# Sensors.net
KiCad netlist of a schematic drawn in Altium Designer
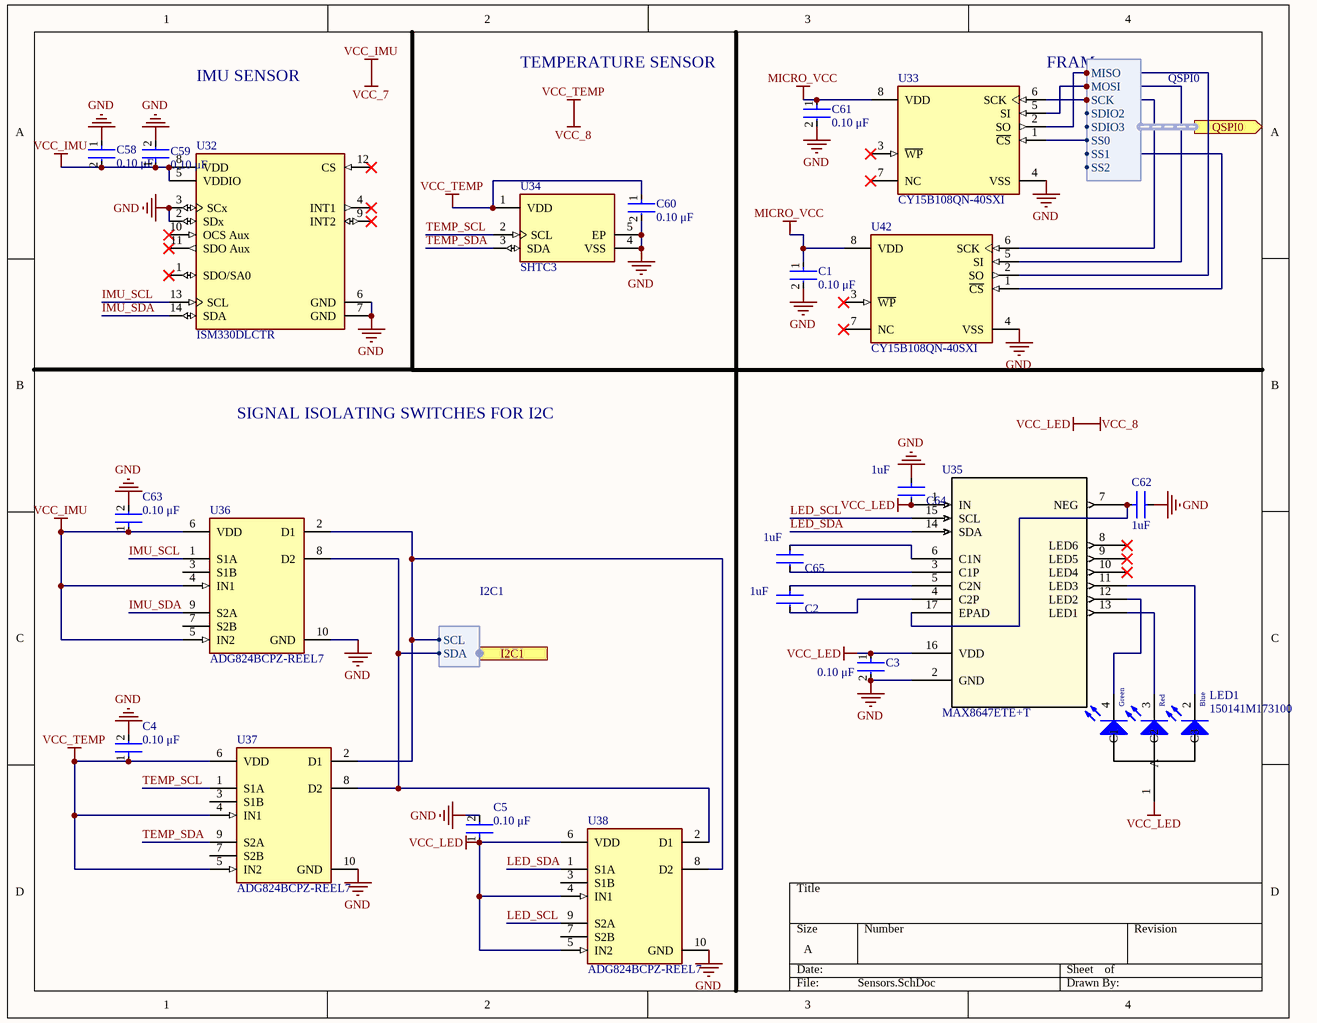
[diagram p0: Sensors.SchDoc]

(export (version "E")
  (design (tool "Eeschema 10.0.6"))
  (components
    (comp (ref "C1")
      (value "C0402C104K8PACTU")
      (footprint "FP-C0402-BB-MFG")
      (description "CAP CER 0.1UF 10V X5R 0402")
      (fields
        (field (name "CAPACITANCE") "0.10 μF")
        (field (name "MANUFACTURER") "Kemet")
        (field (name "TOLERANCE") "0.1")
      )
      (libsource (lib "Altium Content Vault") (part "b4654b650e69147ec39a6b967a45e02"))
    )
    (comp (ref "C2")
      (value "GRT155R61C105KE01J")
      (footprint "FP-GRM15-0_1-MFG")
      (description "CAP CER 1UF 10V X5R 0402")
      (fields
        (field (name "OCTOPART") "https://octopart.com/grm155r61a105ke15d-murata-197442")
        (field (name "MANUFACTURER PART NUMBER") "GRM155R61A105KE15D")
        (field (name "CAPACITANCE") "1uF")
      )
      (libsource (lib "Altium Content Vault") (part "02cd4be3c70576c341d710602a673aa"))
    )
    (comp (ref "C3")
      (value "C0402C104K8PACTU")
      (footprint "FP-C0402-BB-MFG")
      (description "CAP CER 0.1UF 10V X5R 0402")
      (fields
        (field (name "CAPACITANCE") "0.10 μF")
        (field (name "MANUFACTURER") "Kemet")
        (field (name "TOLERANCE") "0.1")
      )
      (libsource (lib "Altium Content Vault") (part "b4654b650e69147ec39a6b967a45e02"))
    )
    (comp (ref "C4")
      (value "C0402C104K8PACTU")
      (footprint "FP-C0402-BB-MFG")
      (description "CAP CER 0.1UF 10V X5R 0402")
      (fields
        (field (name "CAPACITANCE") "0.10 μF")
        (field (name "MANUFACTURER") "Kemet")
        (field (name "TOLERANCE") "0.1")
      )
      (libsource (lib "Altium Content Vault") (part "b4654b650e69147ec39a6b967a45e02"))
    )
    (comp (ref "C5")
      (value "C0402C104K8PACTU")
      (footprint "FP-C0402-BB-MFG")
      (description "CAP CER 0.1UF 10V X5R 0402")
      (fields
        (field (name "CAPACITANCE") "0.10 μF")
        (field (name "MANUFACTURER") "Kemet")
        (field (name "TOLERANCE") "0.1")
      )
      (libsource (lib "Altium Content Vault") (part "b4654b650e69147ec39a6b967a45e02"))
    )
    (comp (ref "C58")
      (value "C0402C104K8PACTU")
      (footprint "FP-C0402-BB-MFG")
      (description "CAP CER 0.1UF 10V X5R 0402")
      (fields
        (field (name "CAPACITANCE") "0.10 μF")
        (field (name "MANUFACTURER") "Kemet")
        (field (name "TOLERANCE") "0.1")
      )
      (libsource (lib "Altium Content Vault") (part "b4654b650e69147ec39a6b967a45e02"))
    )
    (comp (ref "C59")
      (value "C0402C104K8PACTU")
      (footprint "FP-C0402-BB-MFG")
      (description "CAP CER 0.1UF 10V X5R 0402")
      (fields
        (field (name "CAPACITANCE") "0.10 μF")
        (field (name "MANUFACTURER") "Kemet")
        (field (name "TOLERANCE") "0.1")
      )
      (libsource (lib "Altium Content Vault") (part "b4654b650e69147ec39a6b967a45e02"))
    )
    (comp (ref "C60")
      (value "C0402C104K8PACTU")
      (footprint "FP-C0402-BB-MFG")
      (description "CAP CER 0.1UF 10V X5R 0402")
      (fields
        (field (name "CAPACITANCE") "0.10 μF")
        (field (name "MANUFACTURER") "Kemet")
        (field (name "TOLERANCE") "0.1")
      )
      (libsource (lib "Altium Content Vault") (part "b4654b650e69147ec39a6b967a45e02"))
    )
    (comp (ref "C61")
      (value "C0402C104K8PACTU")
      (footprint "FP-C0402-BB-MFG")
      (description "CAP CER 0.1UF 10V X5R 0402")
      (fields
        (field (name "CAPACITANCE") "0.10 μF")
        (field (name "MANUFACTURER") "Kemet")
        (field (name "TOLERANCE") "0.1")
      )
      (libsource (lib "Altium Content Vault") (part "b4654b650e69147ec39a6b967a45e02"))
    )
    (comp (ref "C62")
      (value "GRT155R61C105KE01J")
      (footprint "FP-GRM15-0_1-MFG")
      (description "CAP CER 1UF 10V X5R 0402")
      (fields
        (field (name "OCTOPART") "https://octopart.com/grm155r61a105ke15d-murata-197442")
        (field (name "MANUFACTURER PART NUMBER") "GRM155R61A105KE15D")
        (field (name "CAPACITANCE") "1uF")
      )
      (libsource (lib "Altium Content Vault") (part "02cd4be3c70576c341d710602a673aa"))
    )
    (comp (ref "C63")
      (value "C0402C104K8PACTU")
      (footprint "FP-C0402-BB-MFG")
      (description "CAP CER 0.1UF 10V X5R 0402")
      (fields
        (field (name "CAPACITANCE") "0.10 μF")
        (field (name "MANUFACTURER") "Kemet")
        (field (name "TOLERANCE") "0.1")
      )
      (libsource (lib "Altium Content Vault") (part "b4654b650e69147ec39a6b967a45e02"))
    )
    (comp (ref "C64")
      (value "GRT155R61C105KE01J")
      (footprint "FP-GRM15-0_1-MFG")
      (description "CAP CER 1UF 10V X5R 0402")
      (fields
        (field (name "OCTOPART") "https://octopart.com/grm155r61a105ke15d-murata-197442")
        (field (name "MANUFACTURER PART NUMBER") "GRM155R61A105KE15D")
        (field (name "CAPACITANCE") "1uF")
      )
      (libsource (lib "Altium Content Vault") (part "02cd4be3c70576c341d710602a673aa"))
    )
    (comp (ref "C65")
      (value "GRT155R61C105KE01J")
      (footprint "FP-GRM15-0_1-MFG")
      (description "CAP CER 1UF 10V X5R 0402")
      (fields
        (field (name "OCTOPART") "https://octopart.com/grm155r61a105ke15d-murata-197442")
        (field (name "MANUFACTURER PART NUMBER") "GRM155R61A105KE15D")
        (field (name "CAPACITANCE") "1uF")
      )
      (libsource (lib "Altium Content Vault") (part "02cd4be3c70576c341d710602a673aa"))
    )
    (comp (ref "LED1")
      (value "150141M173100")
      (footprint "3528_A")
      (description "SMD Full-Color Top LED, WL-SFTW, Red & Green & Blue")
      (fields (field (name "MANUFACTURER") "Wuerth Elektronik"))
      (libsource (lib "Altium Content Vault") (part "WE-LED_RGB_A1B2R3G4-4"))
    )
    (comp (ref "U32")
      (value "ISM330DLCTR")
      (footprint "FP-LGA-14L-DM00249496-MFG")
      (description "INEMO INERTIAL MODULE")
      (fields
        (field (name "MANUFACTURER") "STMicroelectronics")
        (field (name "OCTOPART") "https://octopart.com/ism330dlctr-stmicroelectronics-85149243")
      )
      (libsource (lib "Altium Content Vault") (part "7cb83b91da826bd22f6a735c633f5ac"))
    )
    (comp (ref "U33")
      (value "CY15B108QN-40SXI")
      (footprint "FP-001-85261-IPC_C")
      (description "IC FRAM 8MBIT 40MHZ 8EIAJ")
      (libsource (lib "Altium Content Vault") (part "94cc5f17500dd1907c0ebdcd3efa3d4"))
    )
    (comp (ref "U34")
      (value "SHTC3")
      (footprint "FP-SHTC3-MFG")
      (description "SENSOR HUMI/TEMP I2C 2% SMD")
      (fields
        (field (name "MANUFACTURER") "Sensirion")
        (field (name "OCTOPART") "https://octopart.com/shtc3-sensirion-91912225")
      )
      (libsource (lib "Altium Content Vault") (part "92e21da4ceb1e434b50171ab113565b"))
    )
    (comp (ref "U35")
      (value "MAX8647ETE+T")
      (footprint "21-0136_T1633+5_MXM-L")
      (description "No Description Available")
      (fields (field (name "COPYRIGHT") "Copyright (C) 2021 Accelerated Designs. All rights reserved"))
      (libsource (lib "2021-07-18_11-49-46") (part "MAX8647ETE+T"))
    )
    (comp (ref "U36")
      (value "ADG824BCPZ-REEL7")
      (footprint "FP-CP-10-10-MFG")
      (description "IC SWITCH DUAL SPDT 10LFCSP")
      (fields
        (field (name "OCTOPART") "https://octopart.com/adg824bcpz-reel7-analog+devices-12410880")
        (field (name "MANUFACTURER") "Analog Devices")
      )
      (libsource (lib "Altium Content Vault") (part "750f7653eda72c1ba3820f182f788e1"))
    )
    (comp (ref "U37")
      (value "ADG824BCPZ-REEL7")
      (footprint "FP-CP-10-10-MFG")
      (description "IC SWITCH DUAL SPDT 10LFCSP")
      (fields
        (field (name "OCTOPART") "https://octopart.com/adg824bcpz-reel7-analog+devices-12410880")
        (field (name "MANUFACTURER") "Analog Devices")
      )
      (libsource (lib "Altium Content Vault") (part "750f7653eda72c1ba3820f182f788e1"))
    )
    (comp (ref "U38")
      (value "ADG824BCPZ-REEL7")
      (footprint "FP-CP-10-10-MFG")
      (description "IC SWITCH DUAL SPDT 10LFCSP")
      (fields
        (field (name "OCTOPART") "https://octopart.com/adg824bcpz-reel7-analog+devices-12410880")
        (field (name "MANUFACTURER") "Analog Devices")
      )
      (libsource (lib "Altium Content Vault") (part "750f7653eda72c1ba3820f182f788e1"))
    )
    (comp (ref "U42")
      (value "CY15B108QN-40SXI")
      (footprint "FP-001-85261-IPC_C")
      (description "IC FRAM 8MBIT 40MHZ 8EIAJ")
      (libsource (lib "Altium Content Vault") (part "94cc5f17500dd1907c0ebdcd3efa3d4"))
    )
  )
  (nets
    (net (code "3") (name "/IMU_SCL") (class "Default")
      (node (ref "U32") (pin "13") (pinfunction "SCL_13") (pintype "input"))
      (node (ref "U36") (pin "1") (pinfunction "S1A_1") (pintype "passive"))
    )
    (net (code "4") (name "/IMU_SDA") (class "Default")
      (node (ref "U32") (pin "14") (pinfunction "SDA_14") (pintype "bidirectional"))
      (node (ref "U36") (pin "9") (pinfunction "S2A_9") (pintype "passive"))
    )
    (net (code "5") (name "/LED_SCL") (class "Default")
      (node (ref "U35") (pin "15") (pinfunction "SCL_15") (pintype "input"))
      (node (ref "U38") (pin "9") (pinfunction "S2A_9") (pintype "passive"))
    )
    (net (code "6") (name "/LED_SDA") (class "Default")
      (node (ref "U35") (pin "14") (pinfunction "SDA_14") (pintype "input"))
      (node (ref "U38") (pin "1") (pinfunction "S1A_1") (pintype "passive"))
    )
    (net (code "7") (name "/MISO") (class "Default")
      (node (ref "U33") (pin "2") (pinfunction "SO_2") (pintype "output"))
      (node (ref "U42") (pin "2") (pinfunction "SO_2") (pintype "output"))
    )
    (net (code "8") (name "/MOSI") (class "Default")
      (node (ref "U33") (pin "5") (pinfunction "SI_5") (pintype "input"))
      (node (ref "U42") (pin "5") (pinfunction "SI_5") (pintype "input"))
    )
    (net (code "9") (name "/SCK") (class "Default")
      (node (ref "U33") (pin "6") (pinfunction "SCK_6") (pintype "input"))
      (node (ref "U42") (pin "6") (pinfunction "SCK_6") (pintype "input"))
    )
    (net (code "10") (name "/SCL") (class "Default")
      (node (ref "U36") (pin "2") (pinfunction "D1_2") (pintype "passive"))
      (node (ref "U37") (pin "2") (pinfunction "D1_2") (pintype "passive"))
      (node (ref "U38") (pin "8") (pinfunction "D2_8") (pintype "passive"))
    )
    (net (code "11") (name "/SDA") (class "Default")
      (node (ref "U36") (pin "8") (pinfunction "D2_8") (pintype "passive"))
      (node (ref "U37") (pin "8") (pinfunction "D2_8") (pintype "passive"))
      (node (ref "U38") (pin "2") (pinfunction "D1_2") (pintype "passive"))
    )
    (net (code "12") (name "/SS0") (class "Default")
      (node (ref "U33") (pin "1") (pinfunction "~{CS}_1") (pintype "input"))
    )
    (net (code "13") (name "/SS1") (class "Default")
      (node (ref "U42") (pin "1") (pinfunction "~{CS}_1") (pintype "input"))
    )
    (net (code "14") (name "/TEMP_SCL") (class "Default")
      (node (ref "U34") (pin "2") (pinfunction "SCL_2") (pintype "input"))
      (node (ref "U37") (pin "1") (pinfunction "S1A_1") (pintype "passive"))
    )
    (net (code "15") (name "/TEMP_SDA") (class "Default")
      (node (ref "U34") (pin "3") (pinfunction "SDA_3") (pintype "bidirectional"))
      (node (ref "U37") (pin "9") (pinfunction "S2A_9") (pintype "passive"))
    )
    (net (code "18") (name "GND") (class "Default")
      (node (ref "C1") (pin "2") (pinfunction "2_2") (pintype "passive"))
      (node (ref "C3") (pin "2") (pinfunction "2_2") (pintype "passive"))
      (node (ref "C4") (pin "2") (pinfunction "2_2") (pintype "passive"))
      (node (ref "C5") (pin "2") (pinfunction "2_2") (pintype "passive"))
      (node (ref "C58") (pin "1") (pinfunction "1_1") (pintype "passive"))
      (node (ref "C59") (pin "2") (pinfunction "2_2") (pintype "passive"))
      (node (ref "C60") (pin "2") (pinfunction "2_2") (pintype "passive"))
      (node (ref "C61") (pin "2") (pinfunction "2_2") (pintype "passive"))
      (node (ref "C62") (pin "2") (pinfunction "2_2") (pintype "passive"))
      (node (ref "C63") (pin "2") (pinfunction "2_2") (pintype "passive"))
      (node (ref "C64") (pin "1") (pinfunction "1_1") (pintype "passive"))
      (node (ref "U32") (pin "2") (pinfunction "SDx_2") (pintype "bidirectional"))
      (node (ref "U32") (pin "3") (pinfunction "SCx_3") (pintype "bidirectional"))
      (node (ref "U32") (pin "6") (pinfunction "GND_6") (pintype "power_in"))
      (node (ref "U32") (pin "7") (pinfunction "GND_7") (pintype "power_in"))
      (node (ref "U33") (pin "4") (pinfunction "VSS_4") (pintype "power_in"))
      (node (ref "U34") (pin "4") (pinfunction "VSS_4") (pintype "power_in"))
      (node (ref "U34") (pin "5") (pinfunction "EP_5") (pintype "power_in"))
      (node (ref "U35") (pin "2") (pinfunction "GND_2") (pintype "power_in"))
      (node (ref "U36") (pin "10") (pinfunction "GND_10") (pintype "power_in"))
      (node (ref "U37") (pin "10") (pinfunction "GND_10") (pintype "power_in"))
      (node (ref "U38") (pin "10") (pinfunction "GND_10") (pintype "power_in"))
      (node (ref "U42") (pin "4") (pinfunction "VSS_4") (pintype "power_in"))
    )
    (net (code "19") (name "MICRO_VCC") (class "Default")
      (node (ref "C1") (pin "1") (pinfunction "1_1") (pintype "passive"))
      (node (ref "C61") (pin "1") (pinfunction "1_1") (pintype "passive"))
      (node (ref "U33") (pin "8") (pinfunction "VDD_8") (pintype "power_in"))
      (node (ref "U42") (pin "8") (pinfunction "VDD_8") (pintype "power_in"))
    )
    (net (code "20") (name "Net-(LED1-C1)") (class "Default")
      (node (ref "LED1") (pin "4") (pinfunction "C1_4") (pintype "passive"))
      (node (ref "U35") (pin "12") (pinfunction "LED2_12") (pintype "output"))
    )
    (net (code "21") (name "Net-(LED1-C2)") (class "Default")
      (node (ref "LED1") (pin "3") (pinfunction "C2_3") (pintype "passive"))
      (node (ref "U35") (pin "13") (pinfunction "LED1_13") (pintype "output"))
    )
    (net (code "22") (name "Net-(LED1-C3)") (class "Default")
      (node (ref "LED1") (pin "2") (pinfunction "C3_2") (pintype "passive"))
      (node (ref "U35") (pin "11") (pinfunction "LED3_11") (pintype "output"))
    )
    (net (code "23") (name "Net-(U35-C1N)") (class "Default")
      (node (ref "C65") (pin "1") (pinfunction "1_1") (pintype "passive"))
      (node (ref "U35") (pin "6") (pinfunction "C1N_6") (pintype "passive"))
    )
    (net (code "24") (name "Net-(U35-C1P)") (class "Default")
      (node (ref "C65") (pin "2") (pinfunction "2_2") (pintype "passive"))
      (node (ref "U35") (pin "3") (pinfunction "C1P_3") (pintype "passive"))
    )
    (net (code "25") (name "Net-(U35-C2N)") (class "Default")
      (node (ref "C2") (pin "1") (pinfunction "1_1") (pintype "passive"))
      (node (ref "U35") (pin "5") (pinfunction "C2N_5") (pintype "passive"))
    )
    (net (code "26") (name "Net-(U35-C2P)") (class "Default")
      (node (ref "C2") (pin "2") (pinfunction "2_2") (pintype "passive"))
      (node (ref "U35") (pin "4") (pinfunction "C2P_4") (pintype "passive"))
    )
    (net (code "27") (name "Net-(U35-EPAD)") (class "Default")
      (node (ref "C62") (pin "1") (pinfunction "1_1") (pintype "passive"))
      (node (ref "U35") (pin "17") (pinfunction "EPAD_17") (pintype "passive"))
      (node (ref "U35") (pin "7") (pinfunction "NEG_7") (pintype "output"))
    )
    (net (code "28") (name "VCC_7") (class "Default")
      (node (ref "C58") (pin "2") (pinfunction "2_2") (pintype "passive"))
      (node (ref "C59") (pin "1") (pinfunction "1_1") (pintype "passive"))
      (node (ref "C63") (pin "1") (pinfunction "1_1") (pintype "passive"))
      (node (ref "U32") (pin "5") (pinfunction "VDDIO_5") (pintype "power_in"))
      (node (ref "U32") (pin "8") (pinfunction "VDD_8") (pintype "power_in"))
      (node (ref "U36") (pin "4") (pinfunction "IN1_4") (pintype "input"))
      (node (ref "U36") (pin "5") (pinfunction "IN2_5") (pintype "input"))
      (node (ref "U36") (pin "6") (pinfunction "VDD_6") (pintype "power_in"))
    )
    (net (code "29") (name "VCC_8") (class "Default")
      (node (ref "C3") (pin "1") (pinfunction "1_1") (pintype "passive"))
      (node (ref "C4") (pin "1") (pinfunction "1_1") (pintype "passive"))
      (node (ref "C5") (pin "1") (pinfunction "1_1") (pintype "passive"))
      (node (ref "C60") (pin "1") (pinfunction "1_1") (pintype "passive"))
      (node (ref "C64") (pin "2") (pinfunction "2_2") (pintype "passive"))
      (node (ref "LED1") (pin "1") (pinfunction "A_1") (pintype "passive"))
      (node (ref "U34") (pin "1") (pinfunction "VDD_1") (pintype "power_in"))
      (node (ref "U35") (pin "1") (pinfunction "IN_1") (pintype "input"))
      (node (ref "U35") (pin "16") (pinfunction "VDD_16") (pintype "power_in"))
      (node (ref "U37") (pin "4") (pinfunction "IN1_4") (pintype "input"))
      (node (ref "U37") (pin "5") (pinfunction "IN2_5") (pintype "input"))
      (node (ref "U37") (pin "6") (pinfunction "VDD_6") (pintype "power_in"))
      (node (ref "U38") (pin "4") (pinfunction "IN1_4") (pintype "input"))
      (node (ref "U38") (pin "5") (pinfunction "IN2_5") (pintype "input"))
      (node (ref "U38") (pin "6") (pinfunction "VDD_6") (pintype "power_in"))
    )
    (net (code "30") (name "unconnected-(U32-CS-Pad12)") (class "Default")
      (node (ref "U32") (pin "12") (pinfunction "CS_12") (pintype "input+no_connect"))
    )
    (net (code "31") (name "unconnected-(U32-INT1-Pad4)") (class "Default")
      (node (ref "U32") (pin "4") (pinfunction "INT1_4") (pintype "output+no_connect"))
    )
    (net (code "32") (name "unconnected-(U32-INT2-Pad9)") (class "Default")
      (node (ref "U32") (pin "9") (pinfunction "INT2_9") (pintype "bidirectional+no_connect"))
    )
    (net (code "33") (name "unconnected-(U32-OCS_Aux-Pad10)") (class "Default")
      (node (ref "U32") (pin "10") (pinfunction "OCS_Aux_10") (pintype "input+no_connect"))
    )
    (net (code "34") (name "unconnected-(U32-SDO_Aux-Pad11)") (class "Default")
      (node (ref "U32") (pin "11") (pinfunction "SDO_Aux_11") (pintype "output+no_connect"))
    )
    (net (code "35") (name "unconnected-(U32-SDO{slash}SA0-Pad1)") (class "Default")
      (node (ref "U32") (pin "1") (pinfunction "SDO/SA0_1") (pintype "bidirectional+no_connect"))
    )
    (net (code "36") (name "unconnected-(U33-NC-Pad7)") (class "Default")
      (node (ref "U33") (pin "7") (pinfunction "NC_7") (pintype "passive+no_connect"))
    )
    (net (code "37") (name "unconnected-(U33-~{WP}-Pad3)") (class "Default")
      (node (ref "U33") (pin "3") (pinfunction "~{WP}_3") (pintype "input+no_connect"))
    )
    (net (code "38") (name "unconnected-(U35-LED4-Pad10)") (class "Default")
      (node (ref "U35") (pin "10") (pinfunction "LED4_10") (pintype "output+no_connect"))
    )
    (net (code "39") (name "unconnected-(U35-LED5-Pad9)") (class "Default")
      (node (ref "U35") (pin "9") (pinfunction "LED5_9") (pintype "output+no_connect"))
    )
    (net (code "40") (name "unconnected-(U35-LED6-Pad8)") (class "Default")
      (node (ref "U35") (pin "8") (pinfunction "LED6_8") (pintype "output+no_connect"))
    )
    (net (code "41") (name "unconnected-(U36-S1B-Pad3)") (class "Default")
      (node (ref "U36") (pin "3") (pinfunction "S1B_3") (pintype "passive"))
    )
    (net (code "42") (name "unconnected-(U36-S2B-Pad7)") (class "Default")
      (node (ref "U36") (pin "7") (pinfunction "S2B_7") (pintype "passive"))
    )
    (net (code "43") (name "unconnected-(U37-S1B-Pad3)") (class "Default")
      (node (ref "U37") (pin "3") (pinfunction "S1B_3") (pintype "passive"))
    )
    (net (code "44") (name "unconnected-(U37-S2B-Pad7)") (class "Default")
      (node (ref "U37") (pin "7") (pinfunction "S2B_7") (pintype "passive"))
    )
    (net (code "45") (name "unconnected-(U38-S1B-Pad3)") (class "Default")
      (node (ref "U38") (pin "3") (pinfunction "S1B_3") (pintype "passive"))
    )
    (net (code "46") (name "unconnected-(U38-S2B-Pad7)") (class "Default")
      (node (ref "U38") (pin "7") (pinfunction "S2B_7") (pintype "passive"))
    )
    (net (code "47") (name "unconnected-(U42-NC-Pad7)") (class "Default")
      (node (ref "U42") (pin "7") (pinfunction "NC_7") (pintype "passive+no_connect"))
    )
    (net (code "48") (name "unconnected-(U42-~{WP}-Pad3)") (class "Default")
      (node (ref "U42") (pin "3") (pinfunction "~{WP}_3") (pintype "input+no_connect"))
    )
  )
)
